# 2RelayModule.net
KiCad netlist of a schematic drawn in EAGLE
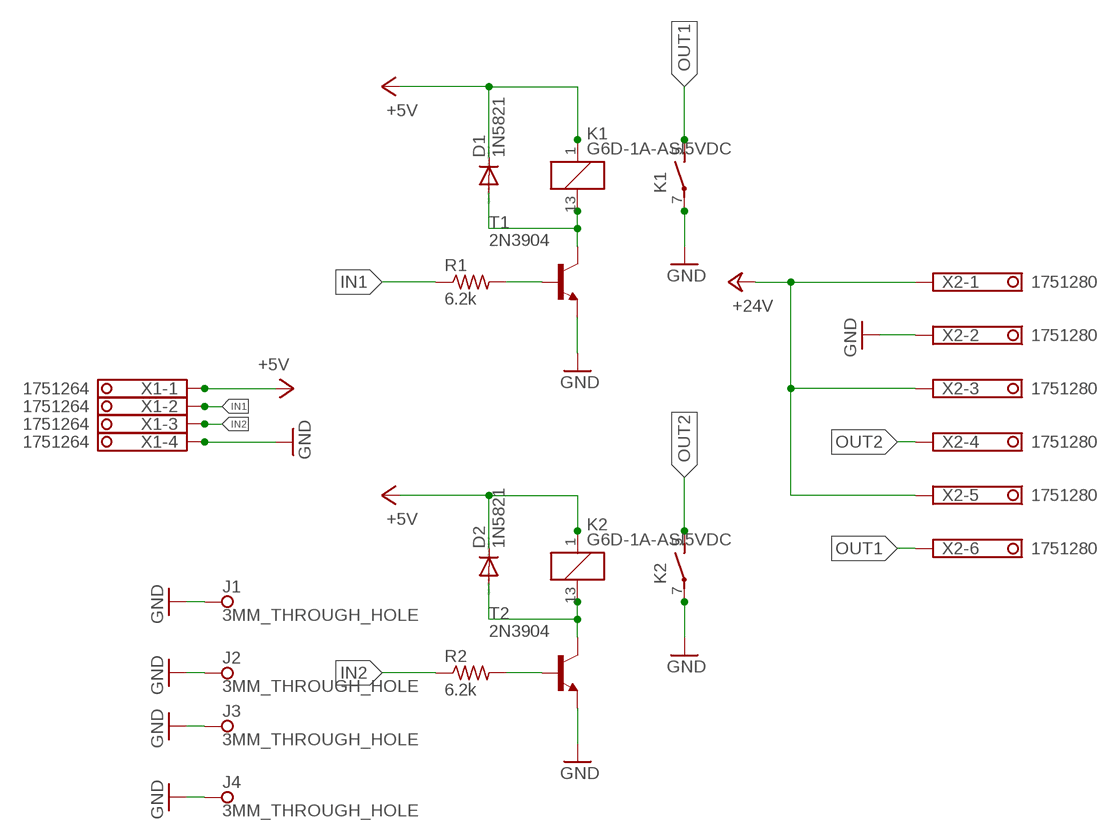
[diagram p0: schematic, sheet 1]

(export (version "E")
  (design (tool "Eeschema 10.0.6"))
  (components
    (comp (ref "D1")
      (value "1N5821")
      (footprint "eagle-import:DO41-10")
      (libsource (lib "eagle-import") (part "1N4004"))
    )
    (comp (ref "D2")
      (value "1N5821")
      (footprint "eagle-import:DO41-10")
      (libsource (lib "eagle-import") (part "1N4004"))
    )
    (comp (ref "J1")
      (value "3MM_THROUGH_HOLE")
      (footprint "eagle-import:3MM_THROUGH_HOLE")
      (libsource (lib "eagle-import") (part "3MM_THROUGH_HOLE"))
    )
    (comp (ref "J2")
      (value "3MM_THROUGH_HOLE")
      (footprint "eagle-import:3MM_THROUGH_HOLE")
      (libsource (lib "eagle-import") (part "3MM_THROUGH_HOLE"))
    )
    (comp (ref "J3")
      (value "3MM_THROUGH_HOLE")
      (footprint "eagle-import:3MM_THROUGH_HOLE")
      (libsource (lib "eagle-import") (part "3MM_THROUGH_HOLE"))
    )
    (comp (ref "J4")
      (value "3MM_THROUGH_HOLE")
      (footprint "eagle-import:3MM_THROUGH_HOLE")
      (libsource (lib "eagle-import") (part "3MM_THROUGH_HOLE"))
    )
    (comp (ref "K1")
      (value "G6D-1A-ASI5VDC")
      (footprint "eagle-import:G6D")
      (libsource (lib "eagle-import") (part "G6D?-1A-ASI5VDC"))
    )
    (comp (ref "K2")
      (value "G6D-1A-ASI5VDC")
      (footprint "eagle-import:G6D")
      (libsource (lib "eagle-import") (part "G6D?-1A-ASI5VDC"))
    )
    (comp (ref "R1")
      (value "6.2k")
      (footprint "eagle-import:0207_10")
      (libsource (lib "eagle-import") (part "R-US_0207/10"))
    )
    (comp (ref "R2")
      (value "6.2k")
      (footprint "eagle-import:0207_10")
      (libsource (lib "eagle-import") (part "R-US_0207/10"))
    )
    (comp (ref "T1")
      (value "2N3904")
      (footprint "eagle-import:TO92")
      (libsource (lib "eagle-import") (part "2N3904"))
    )
    (comp (ref "T2")
      (value "2N3904")
      (footprint "eagle-import:TO92")
      (libsource (lib "eagle-import") (part "2N3904"))
    )
    (comp (ref "X1")
      (value "1751264")
      (footprint "eagle-import:1751264")
      (libsource (lib "eagle-import") (part "1751264"))
    )
    (comp (ref "X2")
      (value "1751280")
      (footprint "eagle-import:1751280")
      (libsource (lib "eagle-import") (part "1751280"))
    )
  )
  (nets
    (net (code "1") (name "+5V") (class "Default")
      (node (ref "D1") (pin "C") (pinfunction "C_C") (pintype "passive"))
      (node (ref "D2") (pin "C") (pinfunction "C_C") (pintype "passive"))
      (node (ref "K1") (pin "1") (pinfunction "1_1") (pintype "passive"))
      (node (ref "K2") (pin "1") (pinfunction "1_1") (pintype "passive"))
      (node (ref "X1") (pin "1") (pinfunction "K_1") (pintype "passive"))
    )
    (net (code "2") (name "+24V") (class "Default")
      (node (ref "X2") (pin "1") (pinfunction "K_1") (pintype "passive"))
      (node (ref "X2") (pin "3") (pinfunction "K_3") (pintype "passive"))
      (node (ref "X2") (pin "5") (pinfunction "K_5") (pintype "passive"))
    )
    (net (code "3") (name "GND") (class "Default")
      (node (ref "J1") (pin "HOLE") (pinfunction "1_HOLE") (pintype "passive"))
      (node (ref "J2") (pin "HOLE") (pinfunction "1_HOLE") (pintype "passive"))
      (node (ref "J3") (pin "HOLE") (pinfunction "1_HOLE") (pintype "passive"))
      (node (ref "J4") (pin "HOLE") (pinfunction "1_HOLE") (pintype "passive"))
      (node (ref "K1") (pin "7") (pinfunction "P_7") (pintype "passive"))
      (node (ref "K2") (pin "7") (pinfunction "P_7") (pintype "passive"))
      (node (ref "T1") (pin "3") (pinfunction "E_3") (pintype "passive"))
      (node (ref "T2") (pin "3") (pinfunction "E_3") (pintype "passive"))
      (node (ref "X1") (pin "4") (pinfunction "K_4") (pintype "passive"))
      (node (ref "X2") (pin "2") (pinfunction "K_2") (pintype "passive"))
    )
    (net (code "4") (name "IN1") (class "Default")
      (node (ref "R1") (pin "1") (pinfunction "1_1") (pintype "passive"))
      (node (ref "X1") (pin "2") (pinfunction "K_2") (pintype "passive"))
    )
    (net (code "5") (name "IN2") (class "Default")
      (node (ref "R2") (pin "1") (pinfunction "1_1") (pintype "passive"))
      (node (ref "X1") (pin "3") (pinfunction "K_3") (pintype "passive"))
    )
    (net (code "6") (name "Net-(K1A-2)") (class "Default")
      (node (ref "D1") (pin "A") (pinfunction "A_A") (pintype "passive"))
      (node (ref "K1") (pin "13") (pinfunction "2_13") (pintype "passive"))
      (node (ref "T1") (pin "1") (pinfunction "C_1") (pintype "passive"))
    )
    (net (code "7") (name "Net-(K2A-2)") (class "Default")
      (node (ref "D2") (pin "A") (pinfunction "A_A") (pintype "passive"))
      (node (ref "K2") (pin "13") (pinfunction "2_13") (pintype "passive"))
      (node (ref "T2") (pin "1") (pinfunction "C_1") (pintype "passive"))
    )
    (net (code "8") (name "Net-(T1-B)") (class "Default")
      (node (ref "R1") (pin "2") (pinfunction "2_2") (pintype "passive"))
      (node (ref "T1") (pin "2") (pinfunction "B_2") (pintype "passive"))
    )
    (net (code "9") (name "Net-(T2-B)") (class "Default")
      (node (ref "R2") (pin "2") (pinfunction "2_2") (pintype "passive"))
      (node (ref "T2") (pin "2") (pinfunction "B_2") (pintype "passive"))
    )
    (net (code "10") (name "OUT1") (class "Default")
      (node (ref "K1") (pin "5") (pinfunction "S_5") (pintype "passive"))
      (node (ref "X2") (pin "6") (pinfunction "K_6") (pintype "passive"))
    )
    (net (code "11") (name "OUT2") (class "Default")
      (node (ref "K2") (pin "5") (pinfunction "S_5") (pintype "passive"))
      (node (ref "X2") (pin "4") (pinfunction "K_4") (pintype "passive"))
    )
  )
)
